# amp.net
KiCad netlist of a schematic drawn in EAGLE
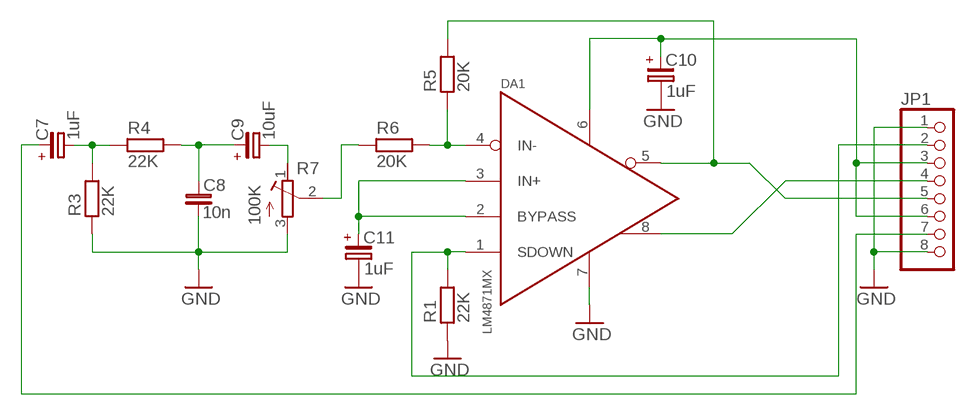
[diagram p0: schematic, sheet 1]

(export (version "E")
  (design (tool "Eeschema 10.0.6"))
  (components
    (comp (ref "C7")
      (value "1uF")
      (footprint "eagle-import:SMC_A")
      (libsource (lib "eagle-import") (part "CP_SMCA"))
    )
    (comp (ref "C8")
      (value "10n")
      (footprint "eagle-import:C0805")
      (libsource (lib "eagle-import") (part "C_0805"))
    )
    (comp (ref "C9")
      (value "10uF")
      (footprint "eagle-import:SMC_A")
      (libsource (lib "eagle-import") (part "CP_SMCA"))
    )
    (comp (ref "C10")
      (value "1uF")
      (footprint "eagle-import:SMC_B")
      (libsource (lib "eagle-import") (part "CP_SMCB"))
    )
    (comp (ref "C11")
      (value "1uF")
      (footprint "eagle-import:SMC_A")
      (libsource (lib "eagle-import") (part "CP_SMCA"))
    )
    (comp (ref "DA1")
      (value "LM4871MX")
      (footprint "eagle-import:SO08")
      (libsource (lib "eagle-import") (part "LM4871MX"))
    )
    (comp (ref "JP1")
      (value "PINHD-1X8_2.54-90°")
      (footprint "eagle-import:1X08_90")
      (libsource (lib "eagle-import") (part "PINHD-1X8_2.54-90°"))
    )
    (comp (ref "R1")
      (value "22K")
      (footprint "eagle-import:R0805")
      (libsource (lib "eagle-import") (part "R_0805"))
    )
    (comp (ref "R3")
      (value "22K")
      (footprint "eagle-import:R0805")
      (libsource (lib "eagle-import") (part "R_0805"))
    )
    (comp (ref "R4")
      (value "22K")
      (footprint "eagle-import:R0805")
      (libsource (lib "eagle-import") (part "R_0805"))
    )
    (comp (ref "R5")
      (value "20K")
      (footprint "eagle-import:R0805")
      (libsource (lib "eagle-import") (part "R_0805"))
    )
    (comp (ref "R6")
      (value "20K")
      (footprint "eagle-import:R0805")
      (libsource (lib "eagle-import") (part "R_0805"))
    )
    (comp (ref "R7")
      (value "100K")
      (footprint "eagle-import:RTRIM-3362P")
      (libsource (lib "eagle-import") (part "RTRIM"))
    )
  )
  (nets
    (net (code "1") (name "GND") (class "Default")
      (node (ref "C10") (pin "-") (pinfunction "-_-") (pintype "passive"))
      (node (ref "C11") (pin "-") (pinfunction "-_-") (pintype "passive"))
      (node (ref "C8") (pin "2") (pinfunction "2_2") (pintype "passive"))
      (node (ref "DA1") (pin "7") (pinfunction "GND_7") (pintype "power_in"))
      (node (ref "JP1") (pin "1") (pinfunction "1_1") (pintype "passive"))
      (node (ref "JP1") (pin "8") (pinfunction "8_8") (pintype "passive"))
      (node (ref "R1") (pin "1") (pinfunction "1_1") (pintype "passive"))
      (node (ref "R3") (pin "1") (pinfunction "1_1") (pintype "passive"))
      (node (ref "R7") (pin "3") (pinfunction "E_3") (pintype "passive"))
    )
    (net (code "2") (name "Net-(C7-Pad+)") (class "Default")
      (node (ref "C7") (pin "+") (pinfunction "+_+") (pintype "passive"))
      (node (ref "JP1") (pin "7") (pinfunction "7_7") (pintype "passive"))
    )
    (net (code "3") (name "Net-(C7-Pad-)") (class "Default")
      (node (ref "C7") (pin "-") (pinfunction "-_-") (pintype "passive"))
      (node (ref "R3") (pin "2") (pinfunction "2_2") (pintype "passive"))
      (node (ref "R4") (pin "1") (pinfunction "1_1") (pintype "passive"))
    )
    (net (code "4") (name "Net-(C8-Pad1)") (class "Default")
      (node (ref "C8") (pin "1") (pinfunction "1_1") (pintype "passive"))
      (node (ref "C9") (pin "+") (pinfunction "+_+") (pintype "passive"))
      (node (ref "R4") (pin "2") (pinfunction "2_2") (pintype "passive"))
    )
    (net (code "5") (name "Net-(DA1-BYPASS)") (class "Default")
      (node (ref "C11") (pin "+") (pinfunction "+_+") (pintype "passive"))
      (node (ref "DA1") (pin "2") (pinfunction "BYPASS_2") (pintype "input"))
      (node (ref "DA1") (pin "3") (pinfunction "IN+_3") (pintype "input"))
    )
    (net (code "6") (name "Net-(DA1-IN-)") (class "Default")
      (node (ref "DA1") (pin "4") (pinfunction "IN-_4") (pintype "input"))
      (node (ref "R5") (pin "1") (pinfunction "1_1") (pintype "passive"))
      (node (ref "R6") (pin "2") (pinfunction "2_2") (pintype "passive"))
    )
    (net (code "7") (name "Net-(DA1-OUT+)") (class "Default")
      (node (ref "DA1") (pin "8") (pinfunction "OUT+_8") (pintype "output"))
      (node (ref "JP1") (pin "4") (pinfunction "4_4") (pintype "passive"))
    )
    (net (code "8") (name "Net-(DA1-OUT-)") (class "Default")
      (node (ref "DA1") (pin "5") (pinfunction "OUT-_5") (pintype "output"))
      (node (ref "JP1") (pin "5") (pinfunction "5_5") (pintype "passive"))
      (node (ref "R5") (pin "2") (pinfunction "2_2") (pintype "passive"))
    )
    (net (code "9") (name "Net-(DA1-SDOWN)") (class "Default")
      (node (ref "DA1") (pin "1") (pinfunction "SDOWN_1") (pintype "input"))
      (node (ref "JP1") (pin "2") (pinfunction "2_2") (pintype "passive"))
      (node (ref "R1") (pin "2") (pinfunction "2_2") (pintype "passive"))
    )
    (net (code "10") (name "Net-(DA1-VCC)") (class "Default")
      (node (ref "C10") (pin "+") (pinfunction "+_+") (pintype "passive"))
      (node (ref "DA1") (pin "6") (pinfunction "VCC_6") (pintype "power_in"))
      (node (ref "JP1") (pin "3") (pinfunction "3_3") (pintype "passive"))
      (node (ref "JP1") (pin "6") (pinfunction "6_6") (pintype "passive"))
    )
    (net (code "11") (name "Net-(R7-A)") (class "Default")
      (node (ref "C9") (pin "-") (pinfunction "-_-") (pintype "passive"))
      (node (ref "R7") (pin "1") (pinfunction "A_1") (pintype "passive"))
    )
    (net (code "12") (name "Net-(R7-S)") (class "Default")
      (node (ref "R6") (pin "1") (pinfunction "1_1") (pintype "passive"))
      (node (ref "R7") (pin "2") (pinfunction "S_2") (pintype "passive"))
    )
  )
)
